# PBag.net
KiCad netlist of a schematic drawn in EAGLE
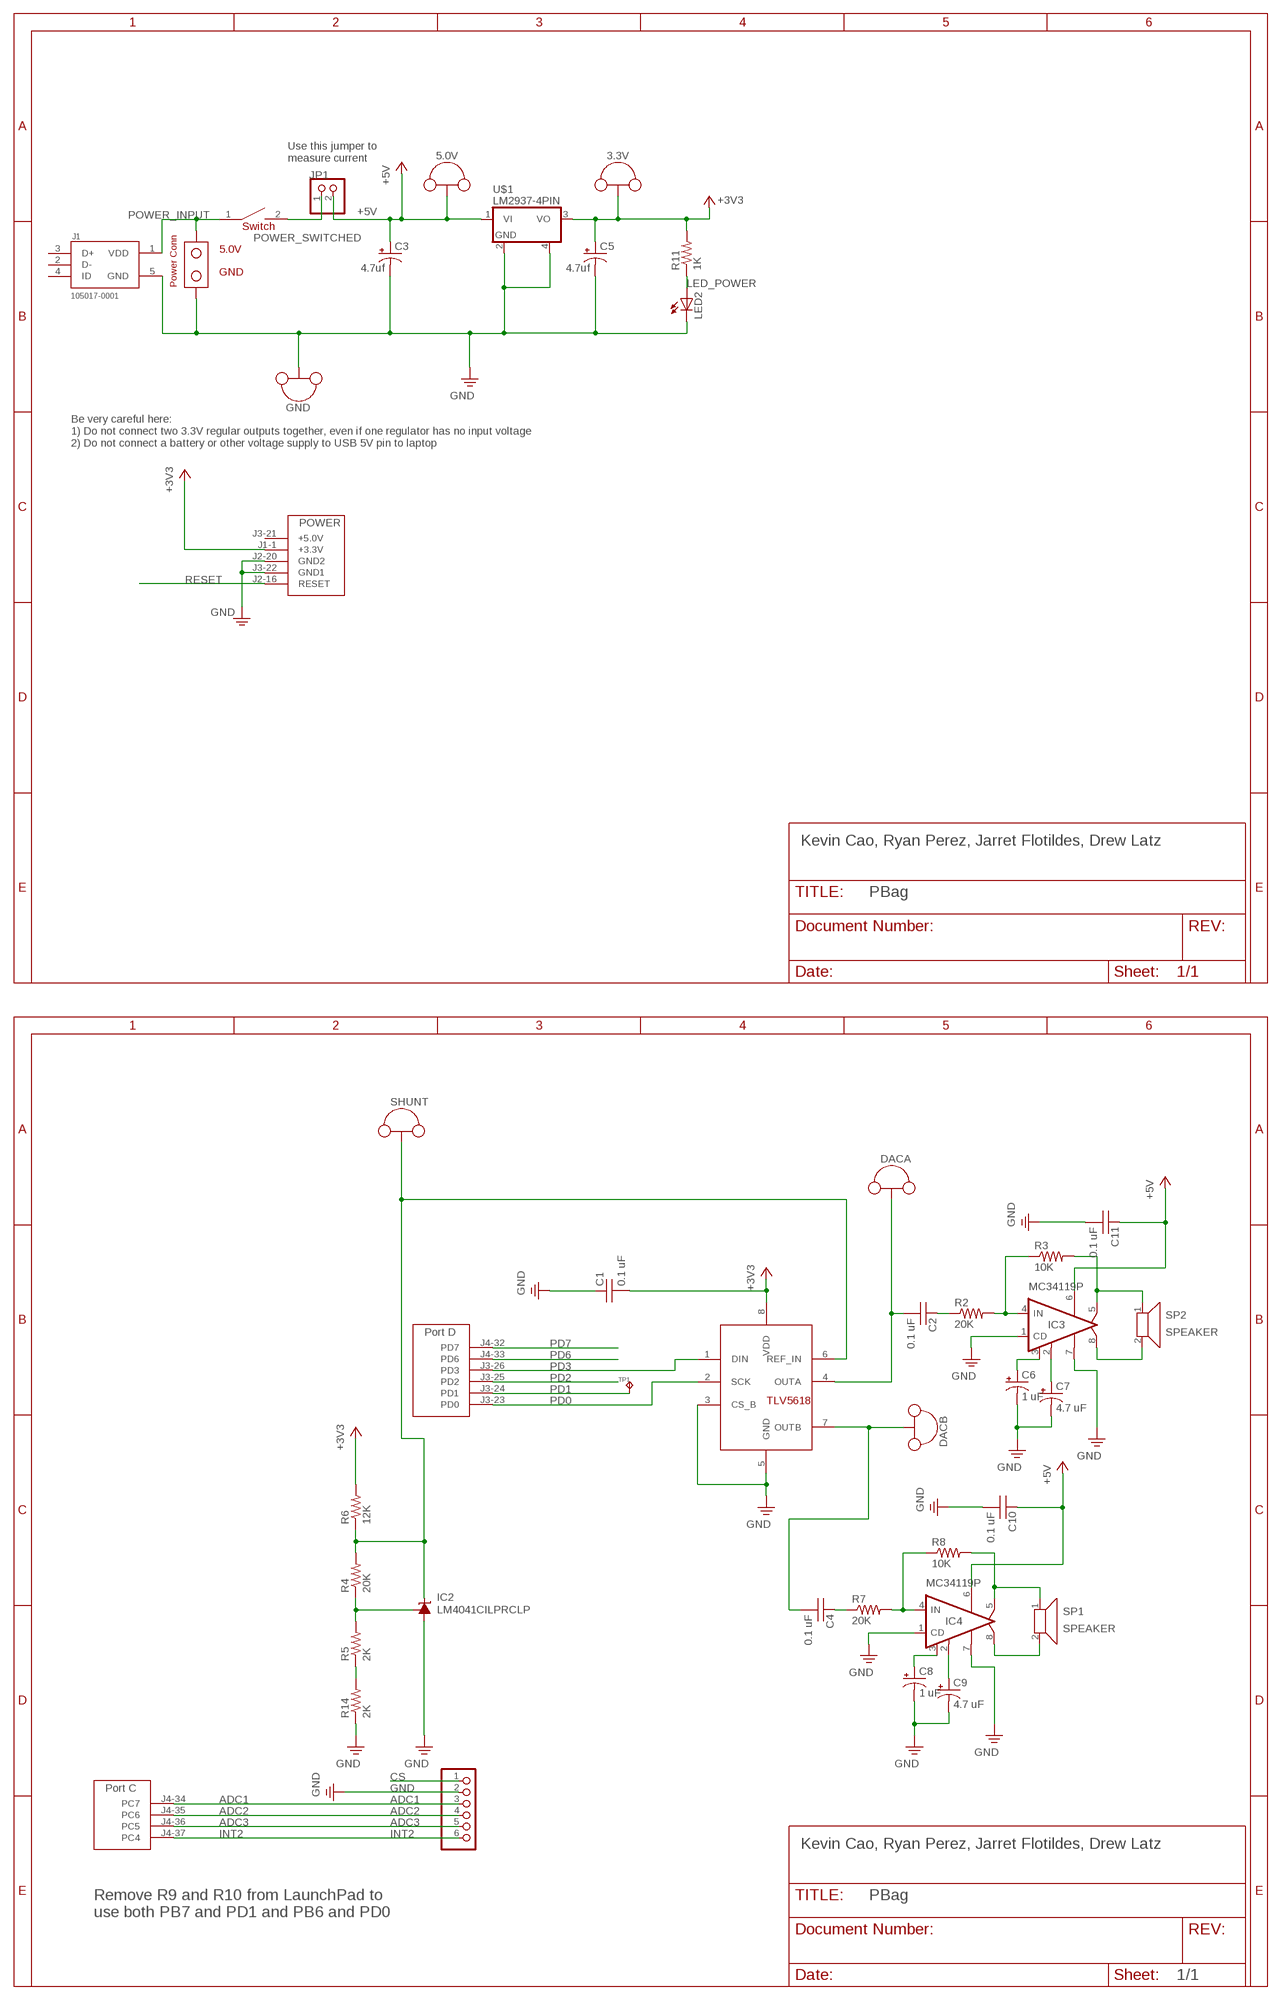
[diagram p0: schematic, sheet 1, part 1 of 2]
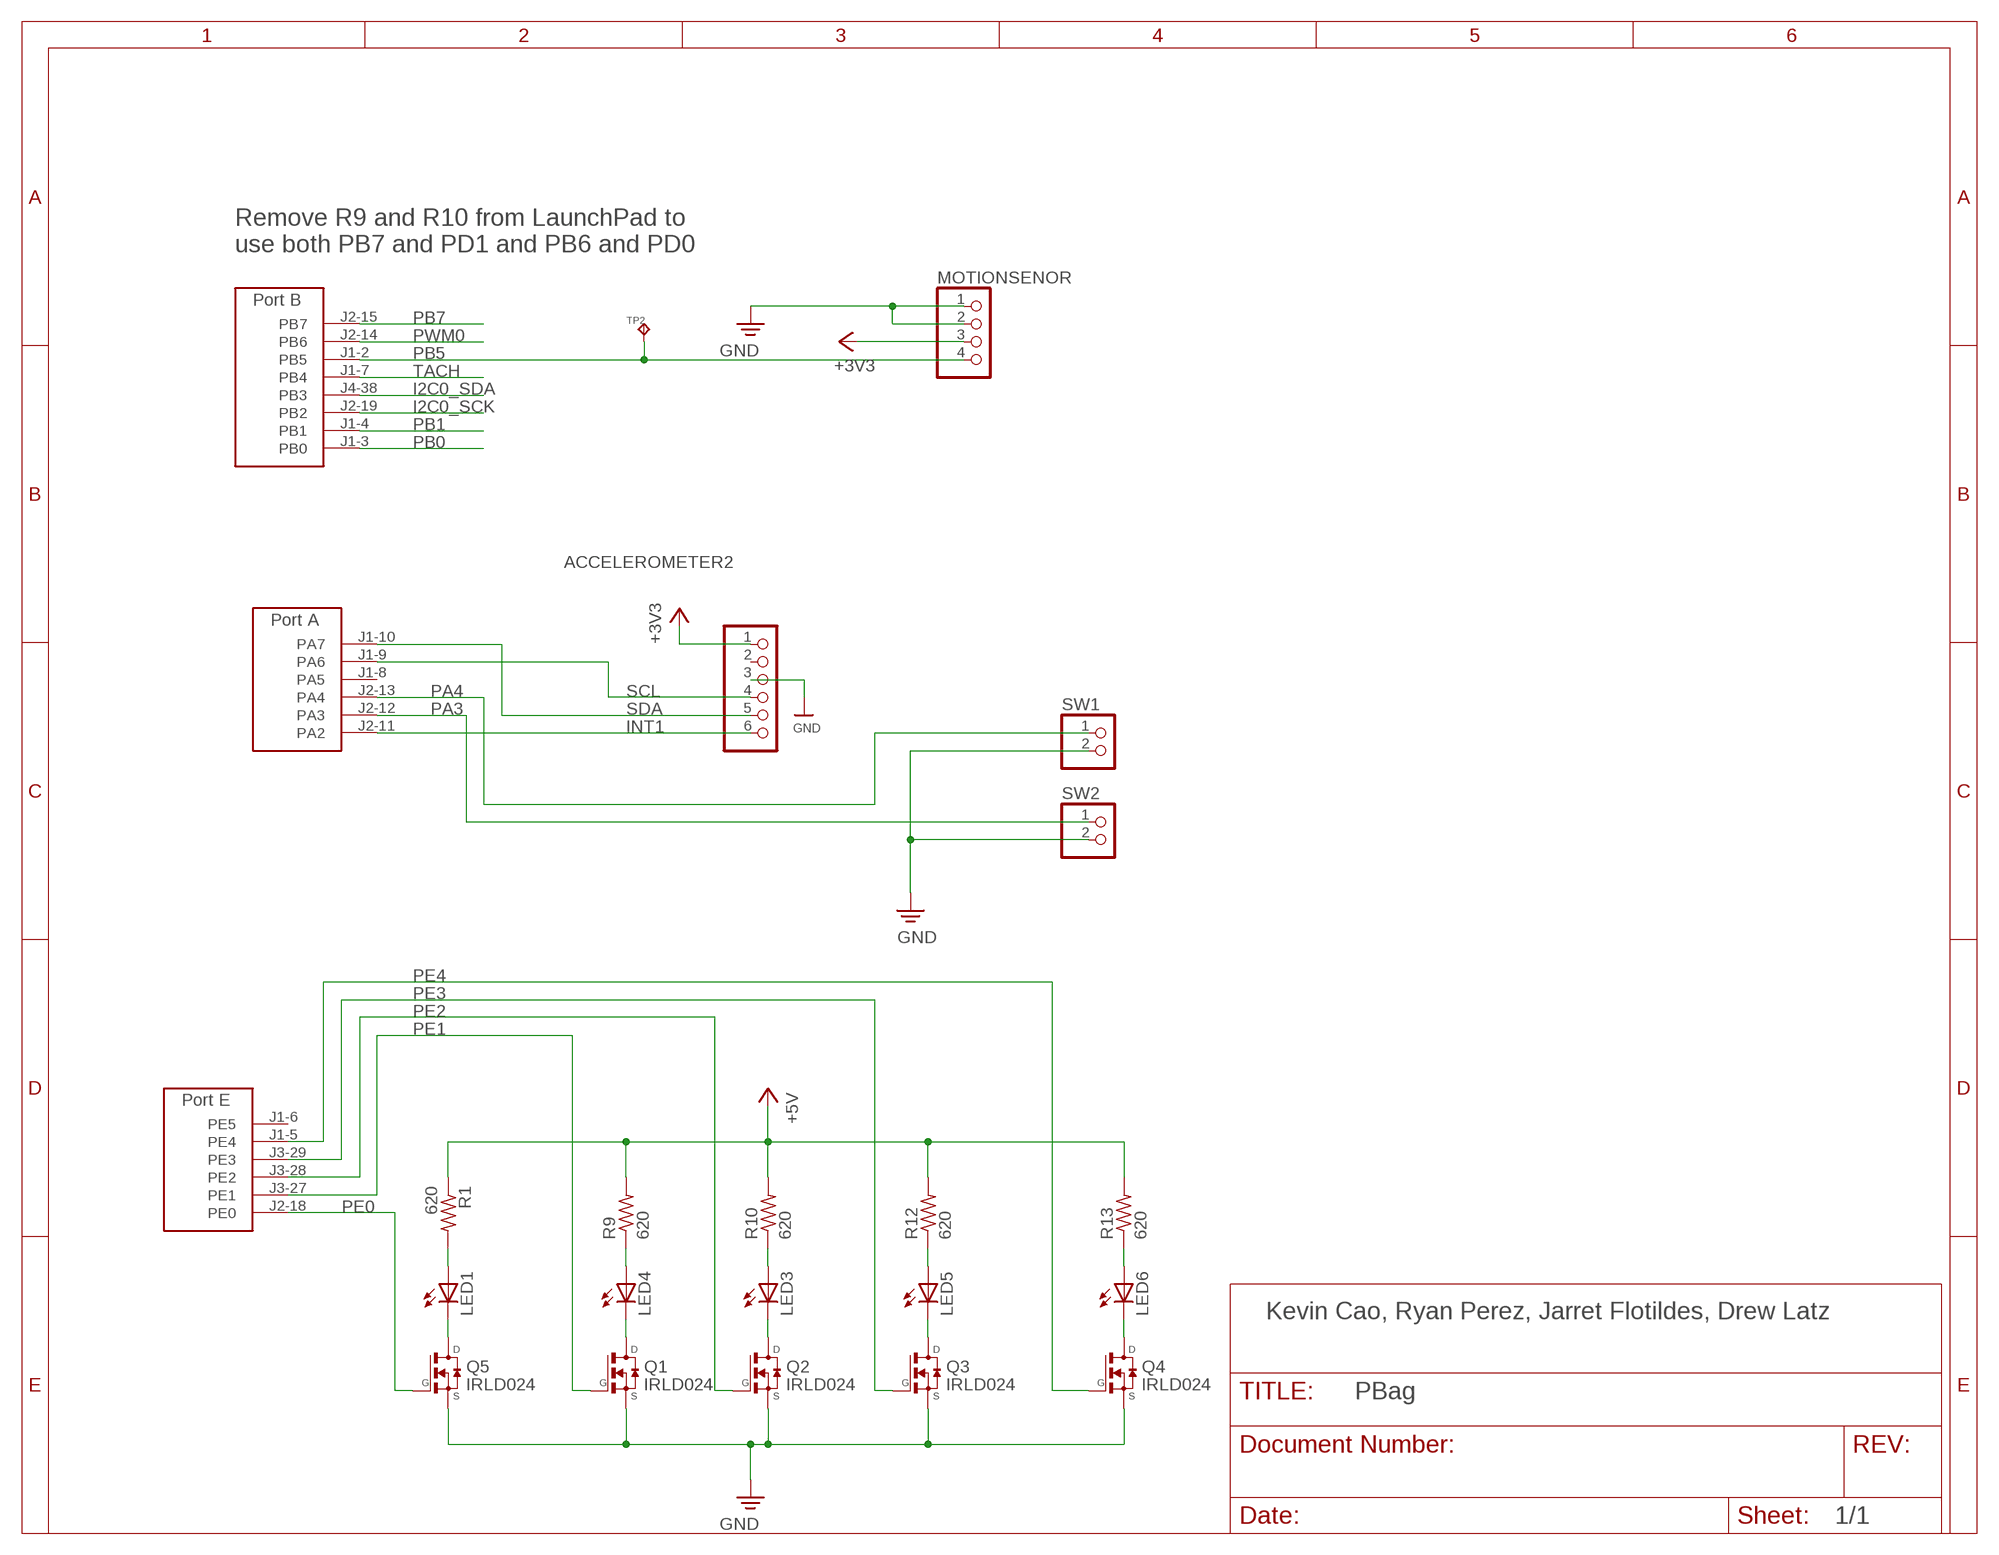
[diagram p1: schematic, sheet 1, part 2 of 2]

(export (version "E")
  (design (tool "Eeschema 10.0.6"))
  (components
    (comp (ref "3.3V")
      (value "TP_LOOP")
      (footprint "eagle-import:TP_LOOP")
      (libsource (lib "eagle-import") (part "TP_LOOP"))
    )
    (comp (ref "5.0V")
      (value "TP_LOOP")
      (footprint "eagle-import:TP_LOOP")
      (libsource (lib "eagle-import") (part "TP_LOOP"))
    )
    (comp (ref "ACCELEROMETER1")
      (value "HEADER-1X670MIL")
      (footprint "eagle-import:1X06_ROUND_70")
      (libsource (lib "eagle-import") (part "HEADER-1X670MIL"))
    )
    (comp (ref "ACCELEROMETER2")
      (value "HEADER-1X670MIL")
      (footprint "eagle-import:1X06_ROUND_70")
      (libsource (lib "eagle-import") (part "HEADER-1X670MIL"))
    )
    (comp (ref "C1")
      (value "0.1 uF")
      (footprint "eagle-import:CAP100MIL")
      (libsource (lib "eagle-import") (part "EE445L (1)_CAPACITOR025-024X044"))
    )
    (comp (ref "C2")
      (value "0.1 uF")
      (footprint "eagle-import:CAP100MIL")
      (libsource (lib "eagle-import") (part "EE445L (1)_CAPACITOR025-024X044"))
    )
    (comp (ref "C3")
      (value "4.7uf")
      (footprint "eagle-import:CAP200MILPOLARIZED")
      (libsource (lib "eagle-import") (part "CAPACITOR_POLARIZEDE5-6"))
    )
    (comp (ref "C4")
      (value "0.1 uF")
      (footprint "eagle-import:CAP100MIL")
      (libsource (lib "eagle-import") (part "EE445L (1)_CAPACITOR025-024X044"))
    )
    (comp (ref "C5")
      (value "4.7uf")
      (footprint "eagle-import:CAP200MILPOLARIZED")
      (libsource (lib "eagle-import") (part "CAPACITOR_POLARIZEDE5-6"))
    )
    (comp (ref "C6")
      (value "1 uF")
      (footprint "eagle-import:CAP200MILPOLARIZED")
      (libsource (lib "eagle-import") (part "EE445L (1)_CAPACITOR_POLARIZEDE5-6"))
    )
    (comp (ref "C7")
      (value "4.7 uF")
      (footprint "eagle-import:CAP200MILPOLARIZED")
      (libsource (lib "eagle-import") (part "EE445L (1)_CAPACITOR_POLARIZEDE5-6"))
    )
    (comp (ref "C8")
      (value "1 uF")
      (footprint "eagle-import:CAP200MILPOLARIZED")
      (libsource (lib "eagle-import") (part "EE445L (1)_CAPACITOR_POLARIZEDE5-6"))
    )
    (comp (ref "C9")
      (value "4.7 uF")
      (footprint "eagle-import:CAP200MILPOLARIZED")
      (libsource (lib "eagle-import") (part "EE445L (1)_CAPACITOR_POLARIZEDE5-6"))
    )
    (comp (ref "C10")
      (value "0.1 uF")
      (footprint "eagle-import:CAP100MIL")
      (libsource (lib "eagle-import") (part "CAPACITOR025-024X044"))
    )
    (comp (ref "C11")
      (value "0.1 uF")
      (footprint "eagle-import:CAP100MIL")
      (libsource (lib "eagle-import") (part "CAPACITOR025-024X044"))
    )
    (comp (ref "DAC")
      (value "TLV5618")
      (footprint "eagle-import:DIL08")
      (libsource (lib "eagle-import") (part "TLV5618"))
    )
    (comp (ref "DACA")
      (value "TP_LOOP")
      (footprint "eagle-import:TP_LOOP")
      (libsource (lib "eagle-import") (part "TP_LOOP"))
    )
    (comp (ref "DACB")
      (value "TP_LOOP")
      (footprint "eagle-import:TP_LOOP")
      (libsource (lib "eagle-import") (part "TP_LOOP"))
    )
    (comp (ref "GND")
      (value "TP_LOOP")
      (footprint "eagle-import:TP_LOOP")
      (libsource (lib "eagle-import") (part "TP_LOOP"))
    )
    (comp (ref "IC2")
      (value "LM4041CILPRCLP")
      (footprint "eagle-import:LP_O-PBCY-W3")
      (fields (field (name "MPN") "LM4041CILP"))
      (libsource (lib "eagle-import") (part "LM4041CILPRLPC"))
    )
    (comp (ref "IC3")
      (value "MC34119P")
      (footprint "eagle-import:DIL08")
      (libsource (lib "eagle-import") (part "MC34119P"))
    )
    (comp (ref "IC4")
      (value "MC34119P")
      (footprint "eagle-import:DIL08")
      (libsource (lib "eagle-import") (part "MC34119P"))
    )
    (comp (ref "J1")
      (value "105017-0001")
      (footprint "eagle-import:MOLEX_105017-0001")
      (fields (field (name "MF") "Molex"))
      (libsource (lib "eagle-import") (part "105017-0001"))
    )
    (comp (ref "JP1")
      (value "PINHD-1X2")
      (footprint "eagle-import:1X02")
      (libsource (lib "eagle-import") (part "PINHD-1X2"))
    )
    (comp (ref "LED1")
      (value "LED5MM")
      (footprint "eagle-import:LED5MM")
      (libsource (lib "eagle-import") (part "EE445L (3)_LED5MM"))
    )
    (comp (ref "LED2")
      (value "LED3MM")
      (footprint "eagle-import:LED3MM")
      (libsource (lib "eagle-import") (part "LED3MM"))
    )
    (comp (ref "LED3")
      (value "LED5MM")
      (footprint "eagle-import:LED5MM")
      (libsource (lib "eagle-import") (part "EE445L (3)_LED5MM"))
    )
    (comp (ref "LED4")
      (value "LED5MM")
      (footprint "eagle-import:LED5MM")
      (libsource (lib "eagle-import") (part "EE445L (3)_LED5MM"))
    )
    (comp (ref "LED5")
      (value "LED5MM")
      (footprint "eagle-import:LED5MM")
      (libsource (lib "eagle-import") (part "EE445L (3)_LED5MM"))
    )
    (comp (ref "LED6")
      (value "LED5MM")
      (footprint "eagle-import:LED5MM")
      (libsource (lib "eagle-import") (part "EE445L (3)_LED5MM"))
    )
    (comp (ref "MOTIONSENOR")
      (value "PINHD-1X4/90")
      (footprint "eagle-import:1X04_90")
      (libsource (lib "eagle-import") (part "PINHD-1X4/90"))
    )
    (comp (ref "Q1")
      (value "IRLD024")
      (footprint "eagle-import:IRLD024")
      (libsource (lib "eagle-import") (part "IRLD024"))
    )
    (comp (ref "Q2")
      (value "IRLD024")
      (footprint "eagle-import:IRLD024")
      (libsource (lib "eagle-import") (part "IRLD024"))
    )
    (comp (ref "Q3")
      (value "IRLD024")
      (footprint "eagle-import:IRLD024")
      (libsource (lib "eagle-import") (part "IRLD024"))
    )
    (comp (ref "Q4")
      (value "IRLD024")
      (footprint "eagle-import:IRLD024")
      (libsource (lib "eagle-import") (part "IRLD024"))
    )
    (comp (ref "Q5")
      (value "IRLD024")
      (footprint "eagle-import:IRLD024")
      (libsource (lib "eagle-import") (part "IRLD024"))
    )
    (comp (ref "R1")
      (value "620")
      (footprint "eagle-import:RES200MIL")
      (libsource (lib "eagle-import") (part "EE445L (3)_RESISTOR0204/5"))
    )
    (comp (ref "R2")
      (value "20K")
      (footprint "eagle-import:RES200MIL")
      (libsource (lib "eagle-import") (part "EE445L (1)_RESISTOR0204/5"))
    )
    (comp (ref "R3")
      (value "10K")
      (footprint "eagle-import:RES200MIL")
      (libsource (lib "eagle-import") (part "EE445L (1)_RESISTOR0204/5"))
    )
    (comp (ref "R4")
      (value "20K")
      (footprint "eagle-import:RES200MIL")
      (libsource (lib "eagle-import") (part "RESISTOR0204/5"))
    )
    (comp (ref "R5")
      (value "2K")
      (footprint "eagle-import:RES200MIL")
      (libsource (lib "eagle-import") (part "RESISTOR0204/5"))
    )
    (comp (ref "R6")
      (value "12K")
      (footprint "eagle-import:RES200MIL")
      (libsource (lib "eagle-import") (part "RESISTOR0204/5"))
    )
    (comp (ref "R7")
      (value "20K")
      (footprint "eagle-import:RES200MIL")
      (libsource (lib "eagle-import") (part "EE445L (1)_RESISTOR0204/5"))
    )
    (comp (ref "R8")
      (value "10K")
      (footprint "eagle-import:RES200MIL")
      (libsource (lib "eagle-import") (part "EE445L (1)_RESISTOR0204/5"))
    )
    (comp (ref "R9")
      (value "620")
      (footprint "eagle-import:RES200MIL")
      (libsource (lib "eagle-import") (part "EE445L (3)_RESISTOR0204/5"))
    )
    (comp (ref "R10")
      (value "620")
      (footprint "eagle-import:RES200MIL")
      (libsource (lib "eagle-import") (part "EE445L (3)_RESISTOR0204/5"))
    )
    (comp (ref "R11")
      (value "1K")
      (footprint "eagle-import:RES200MIL")
      (libsource (lib "eagle-import") (part "RESISTOR0204/5"))
    )
    (comp (ref "R12")
      (value "620")
      (footprint "eagle-import:RES200MIL")
      (libsource (lib "eagle-import") (part "EE445L (3)_RESISTOR0204/5"))
    )
    (comp (ref "R13")
      (value "620")
      (footprint "eagle-import:RES200MIL")
      (libsource (lib "eagle-import") (part "EE445L (3)_RESISTOR0204/5"))
    )
    (comp (ref "R14")
      (value "2K")
      (footprint "eagle-import:RES200MIL")
      (libsource (lib "eagle-import") (part "RESISTOR0204/5"))
    )
    (comp (ref "SHUNT")
      (value "TP_LOOP")
      (footprint "eagle-import:TP_LOOP")
      (libsource (lib "eagle-import") (part "TP_LOOP"))
    )
    (comp (ref "SP1")
      (value "SPEAKER")
      (footprint "eagle-import:1X02")
      (libsource (lib "eagle-import") (part "SPEAKER"))
    )
    (comp (ref "SP2")
      (value "SPEAKER")
      (footprint "eagle-import:1X02")
      (libsource (lib "eagle-import") (part "SPEAKER"))
    )
    (comp (ref "SW1")
      (value "PINHD-1X2")
      (footprint "eagle-import:1X02")
      (libsource (lib "eagle-import") (part "PINHD-1X2"))
    )
    (comp (ref "SW2")
      (value "PINHD-1X2")
      (footprint "eagle-import:1X02")
      (libsource (lib "eagle-import") (part "PINHD-1X2"))
    )
    (comp (ref "TP1")
      (value "TP_KEYSTONE500X")
      (footprint "eagle-import:P1.1MM")
      (libsource (lib "eagle-import") (part "TP_KEYSTONE500X"))
    )
    (comp (ref "TP2")
      (value "TP_KEYSTONE500X")
      (footprint "eagle-import:P1.1MM")
      (libsource (lib "eagle-import") (part "TP_KEYSTONE500X"))
    )
    (comp (ref "U$1")
      (value "LM2937-4PIN")
      (footprint "eagle-import:TO220-4PIN")
      (libsource (lib "eagle-import") (part "LM2937-4PIN"))
    )
    (comp (ref "U$2")
      (value "TM4C_BP")
      (footprint "eagle-import:TM4C_BOOSTER_PACK")
      (libsource (lib "eagle-import") (part "TM4C_BP"))
    )
    (comp (ref "U$5")
      (value "POWER_CONN")
      (footprint "eagle-import:POWER_CONN")
      (libsource (lib "eagle-import") (part "POWER_CONN"))
    )
    (comp (ref "U$6")
      (value "SW_POWER_100MIL")
      (footprint "eagle-import:SW_POWER")
      (libsource (lib "eagle-import") (part "SW_POWER_100MIL"))
    )
  )
  (nets
    (net (code "1") (name "+3V3") (class "Default")
      (node (ref "3.3V") (pin "P$1") (pinfunction "TP_P$1") (pintype "bidirectional"))
      (node (ref "3.3V") (pin "P$2") (pinfunction "TP_P$2") (pintype "bidirectional"))
      (node (ref "ACCELEROMETER2") (pin "1") (pinfunction "1_1") (pintype "passive"))
      (node (ref "C1") (pin "2") (pinfunction "2_2") (pintype "passive"))
      (node (ref "C5") (pin "+") (pinfunction "+_+") (pintype "passive"))
      (node (ref "DAC") (pin "8") (pinfunction "VDD_8") (pintype "bidirectional"))
      (node (ref "MOTIONSENOR") (pin "3") (pinfunction "3_3") (pintype "passive"))
      (node (ref "R11") (pin "2") (pinfunction "2_2") (pintype "passive"))
      (node (ref "R6") (pin "2") (pinfunction "2_2") (pintype "passive"))
      (node (ref "U$1") (pin "3") (pinfunction "VO_3") (pintype "passive"))
      (node (ref "U$2") (pin "J1-1") (pinfunction "+3.3V_J1-1") (pintype "bidirectional"))
    )
    (net (code "2") (name "+5V") (class "Default")
      (node (ref "5.0V") (pin "P$1") (pinfunction "TP_P$1") (pintype "bidirectional"))
      (node (ref "5.0V") (pin "P$2") (pinfunction "TP_P$2") (pintype "bidirectional"))
      (node (ref "C10") (pin "1") (pinfunction "1_1") (pintype "passive"))
      (node (ref "C11") (pin "1") (pinfunction "1_1") (pintype "passive"))
      (node (ref "C3") (pin "+") (pinfunction "+_+") (pintype "passive"))
      (node (ref "IC3") (pin "6") (pinfunction "VCC_6") (pintype "power_in"))
      (node (ref "IC4") (pin "6") (pinfunction "VCC_6") (pintype "power_in"))
      (node (ref "JP1") (pin "2") (pinfunction "2_2") (pintype "passive"))
      (node (ref "R1") (pin "1") (pinfunction "1_1") (pintype "passive"))
      (node (ref "R10") (pin "2") (pinfunction "2_2") (pintype "passive"))
      (node (ref "R12") (pin "2") (pinfunction "2_2") (pintype "passive"))
      (node (ref "R13") (pin "2") (pinfunction "2_2") (pintype "passive"))
      (node (ref "R9") (pin "2") (pinfunction "2_2") (pintype "passive"))
      (node (ref "U$1") (pin "1") (pinfunction "VI_1") (pintype "input"))
    )
    (net (code "3") (name "/ADC1") (class "Default")
      (node (ref "ACCELEROMETER1") (pin "3") (pinfunction "3_3") (pintype "passive"))
      (node (ref "U$2") (pin "J4-34") (pinfunction "PC7_J4-34") (pintype "bidirectional"))
    )
    (net (code "4") (name "/ADC2") (class "Default")
      (node (ref "ACCELEROMETER1") (pin "4") (pinfunction "4_4") (pintype "passive"))
      (node (ref "U$2") (pin "J4-35") (pinfunction "PC6_J4-35") (pintype "bidirectional"))
    )
    (net (code "5") (name "/ADC3") (class "Default")
      (node (ref "ACCELEROMETER1") (pin "5") (pinfunction "5_5") (pintype "passive"))
      (node (ref "U$2") (pin "J4-36") (pinfunction "PC5_J4-36") (pintype "bidirectional"))
    )
    (net (code "6") (name "/CS") (class "Default")
      (node (ref "ACCELEROMETER1") (pin "1") (pinfunction "1_1") (pintype "passive"))
    )
    (net (code "7") (name "/I2C0_SCK") (class "Default")
      (node (ref "U$2") (pin "J2-19") (pinfunction "PB2_J2-19") (pintype "bidirectional"))
    )
    (net (code "8") (name "/I2C0_SDA") (class "Default")
      (node (ref "U$2") (pin "J4-38") (pinfunction "PB3_J4-38") (pintype "bidirectional"))
    )
    (net (code "9") (name "/INT1") (class "Default")
      (node (ref "ACCELEROMETER2") (pin "6") (pinfunction "6_6") (pintype "passive"))
      (node (ref "U$2") (pin "J2-11") (pinfunction "PA2_J2-11") (pintype "bidirectional"))
    )
    (net (code "10") (name "/INT2") (class "Default")
      (node (ref "ACCELEROMETER1") (pin "6") (pinfunction "6_6") (pintype "passive"))
      (node (ref "U$2") (pin "J4-37") (pinfunction "PC4_J4-37") (pintype "bidirectional"))
    )
    (net (code "11") (name "/LED_POWER") (class "Default")
      (node (ref "LED2") (pin "A") (pinfunction "A_A") (pintype "passive"))
      (node (ref "R11") (pin "1") (pinfunction "1_1") (pintype "passive"))
    )
    (net (code "12") (name "/PA3") (class "Default")
      (node (ref "SW2") (pin "1") (pinfunction "1_1") (pintype "passive"))
      (node (ref "U$2") (pin "J2-12") (pinfunction "PA3_J2-12") (pintype "bidirectional"))
    )
    (net (code "13") (name "/PA4") (class "Default")
      (node (ref "SW1") (pin "1") (pinfunction "1_1") (pintype "passive"))
      (node (ref "U$2") (pin "J2-13") (pinfunction "PA4_J2-13") (pintype "bidirectional"))
    )
    (net (code "14") (name "/PB0") (class "Default")
      (node (ref "U$2") (pin "J1-3") (pinfunction "PB0_J1-3") (pintype "bidirectional"))
    )
    (net (code "15") (name "/PB1") (class "Default")
      (node (ref "U$2") (pin "J1-4") (pinfunction "PB1_J1-4") (pintype "bidirectional"))
    )
    (net (code "16") (name "/PB5") (class "Default")
      (node (ref "MOTIONSENOR") (pin "4") (pinfunction "4_4") (pintype "passive"))
      (node (ref "TP2") (pin "TP") (pinfunction "TP_TP") (pintype "input"))
      (node (ref "U$2") (pin "J1-2") (pinfunction "PB5_J1-2") (pintype "bidirectional"))
    )
    (net (code "17") (name "/PB7") (class "Default")
      (node (ref "U$2") (pin "J2-15") (pinfunction "PB7_J2-15") (pintype "bidirectional"))
    )
    (net (code "18") (name "/PD0") (class "Default")
      (node (ref "DAC") (pin "2") (pinfunction "SCK_2") (pintype "bidirectional"))
      (node (ref "U$2") (pin "J3-23") (pinfunction "PD0_J3-23") (pintype "bidirectional"))
    )
    (net (code "19") (name "/PD1") (class "Default")
      (node (ref "TP1") (pin "TP") (pinfunction "TP_TP") (pintype "input"))
      (node (ref "U$2") (pin "J3-24") (pinfunction "PD1_J3-24") (pintype "bidirectional"))
    )
    (net (code "20") (name "/PD2") (class "Default")
      (node (ref "U$2") (pin "J3-25") (pinfunction "PD2_J3-25") (pintype "bidirectional"))
    )
    (net (code "21") (name "/PD3") (class "Default")
      (node (ref "DAC") (pin "1") (pinfunction "DIN_1") (pintype "bidirectional"))
      (node (ref "U$2") (pin "J3-26") (pinfunction "PD3_J3-26") (pintype "bidirectional"))
    )
    (net (code "22") (name "/PD6") (class "Default")
      (node (ref "U$2") (pin "J4-33") (pinfunction "PD6_J4-33") (pintype "bidirectional"))
    )
    (net (code "23") (name "/PD7") (class "Default")
      (node (ref "U$2") (pin "J4-32") (pinfunction "PD7_J4-32") (pintype "bidirectional"))
    )
    (net (code "24") (name "/PE0") (class "Default")
      (node (ref "Q5") (pin "P$3") (pinfunction "G_P$3") (pintype "passive"))
      (node (ref "U$2") (pin "J2-18") (pinfunction "PE0_J2-18") (pintype "bidirectional"))
    )
    (net (code "25") (name "/PE1") (class "Default")
      (node (ref "Q1") (pin "P$3") (pinfunction "G_P$3") (pintype "passive"))
      (node (ref "U$2") (pin "J3-27") (pinfunction "PE1_J3-27") (pintype "bidirectional"))
    )
    (net (code "26") (name "/PE2") (class "Default")
      (node (ref "Q2") (pin "P$3") (pinfunction "G_P$3") (pintype "passive"))
      (node (ref "U$2") (pin "J3-28") (pinfunction "PE2_J3-28") (pintype "bidirectional"))
    )
    (net (code "27") (name "/PE3") (class "Default")
      (node (ref "Q3") (pin "P$3") (pinfunction "G_P$3") (pintype "passive"))
      (node (ref "U$2") (pin "J3-29") (pinfunction "PE3_J3-29") (pintype "bidirectional"))
    )
    (net (code "28") (name "/PE4") (class "Default")
      (node (ref "Q4") (pin "P$3") (pinfunction "G_P$3") (pintype "passive"))
      (node (ref "U$2") (pin "J1-5") (pinfunction "PE4_J1-5") (pintype "bidirectional"))
    )
    (net (code "29") (name "/POWER_INPUT") (class "Default")
      (node (ref "J1") (pin "1") (pinfunction "VDD_1") (pintype "power_in"))
      (node (ref "U$5") (pin "VDD") (pinfunction "VDD_VDD") (pintype "bidirectional"))
      (node (ref "U$6") (pin "1") (pinfunction "P$1_1") (pintype "bidirectional"))
    )
    (net (code "30") (name "/POWER_SWITCHED") (class "Default")
      (node (ref "JP1") (pin "1") (pinfunction "1_1") (pintype "passive"))
      (node (ref "U$6") (pin "2") (pinfunction "P$2_2") (pintype "bidirectional"))
    )
    (net (code "31") (name "/PWM0") (class "Default")
      (node (ref "U$2") (pin "J2-14") (pinfunction "PB6_J2-14") (pintype "bidirectional"))
    )
    (net (code "32") (name "/RESET") (class "Default")
      (node (ref "U$2") (pin "J2-16") (pinfunction "RESET_J2-16") (pintype "bidirectional"))
    )
    (net (code "33") (name "/SCL") (class "Default")
      (node (ref "ACCELEROMETER2") (pin "4") (pinfunction "4_4") (pintype "passive"))
      (node (ref "U$2") (pin "J1-9") (pinfunction "PA6_J1-9") (pintype "bidirectional"))
    )
    (net (code "34") (name "/SDA") (class "Default")
      (node (ref "ACCELEROMETER2") (pin "5") (pinfunction "5_5") (pintype "passive"))
      (node (ref "U$2") (pin "J1-10") (pinfunction "PA7_J1-10") (pintype "bidirectional"))
    )
    (net (code "35") (name "/TACH") (class "Default")
      (node (ref "U$2") (pin "J1-7") (pinfunction "PB4_J1-7") (pintype "bidirectional"))
    )
    (net (code "36") (name "GND") (class "Default")
      (node (ref "ACCELEROMETER1") (pin "2") (pinfunction "2_2") (pintype "passive"))
      (node (ref "ACCELEROMETER2") (pin "3") (pinfunction "3_3") (pintype "passive"))
      (node (ref "C1") (pin "1") (pinfunction "1_1") (pintype "passive"))
      (node (ref "C10") (pin "2") (pinfunction "2_2") (pintype "passive"))
      (node (ref "C11") (pin "2") (pinfunction "2_2") (pintype "passive"))
      (node (ref "C3") (pin "-") (pinfunction "-_-") (pintype "passive"))
      (node (ref "C5") (pin "-") (pinfunction "-_-") (pintype "passive"))
      (node (ref "C6") (pin "-") (pinfunction "-_-") (pintype "passive"))
      (node (ref "C7") (pin "-") (pinfunction "-_-") (pintype "passive"))
      (node (ref "C8") (pin "-") (pinfunction "-_-") (pintype "passive"))
      (node (ref "C9") (pin "-") (pinfunction "-_-") (pintype "passive"))
      (node (ref "DAC") (pin "3") (pinfunction "CS_B_3") (pintype "bidirectional"))
      (node (ref "DAC") (pin "5") (pinfunction "GND_5") (pintype "bidirectional"))
      (node (ref "GND") (pin "P$1") (pinfunction "TP_P$1") (pintype "bidirectional"))
      (node (ref "GND") (pin "P$2") (pinfunction "TP_P$2") (pintype "bidirectional"))
      (node (ref "IC2") (pin "3") (pinfunction "A_3") (pintype "passive"))
      (node (ref "IC3") (pin "1") (pinfunction "CD_1") (pintype "passive"))
      (node (ref "IC3") (pin "7") (pinfunction "GND_7") (pintype "power_in"))
      (node (ref "IC4") (pin "1") (pinfunction "CD_1") (pintype "passive"))
      (node (ref "IC4") (pin "7") (pinfunction "GND_7") (pintype "power_in"))
      (node (ref "J1") (pin "5") (pinfunction "GND_5") (pintype "power_in"))
      (node (ref "LED2") (pin "K") (pinfunction "C_K") (pintype "passive"))
      (node (ref "MOTIONSENOR") (pin "1") (pinfunction "1_1") (pintype "passive"))
      (node (ref "MOTIONSENOR") (pin "2") (pinfunction "2_2") (pintype "passive"))
      (node (ref "Q1") (pin "P$4") (pinfunction "S_P$4") (pintype "passive"))
      (node (ref "Q2") (pin "P$4") (pinfunction "S_P$4") (pintype "passive"))
      (node (ref "Q3") (pin "P$4") (pinfunction "S_P$4") (pintype "passive"))
      (node (ref "Q4") (pin "P$4") (pinfunction "S_P$4") (pintype "passive"))
      (node (ref "Q5") (pin "P$4") (pinfunction "S_P$4") (pintype "passive"))
      (node (ref "R14") (pin "1") (pinfunction "1_1") (pintype "passive"))
      (node (ref "SW1") (pin "2") (pinfunction "2_2") (pintype "passive"))
      (node (ref "SW2") (pin "2") (pinfunction "2_2") (pintype "passive"))
      (node (ref "U$1") (pin "2") (pinfunction "GND_2") (pintype "passive"))
      (node (ref "U$1") (pin "4") (pinfunction "PAD_4") (pintype "passive"))
      (node (ref "U$2") (pin "J2-20") (pinfunction "GND2_J2-20") (pintype "bidirectional"))
      (node (ref "U$2") (pin "J3-22") (pinfunction "GND1_J3-22") (pintype "bidirectional"))
      (node (ref "U$5") (pin "GND") (pinfunction "GND_GND") (pintype "bidirectional"))
    )
    (net (code "37") (name "Net-(C2-Pad1)") (class "Default")
      (node (ref "C2") (pin "1") (pinfunction "1_1") (pintype "passive"))
      (node (ref "R2") (pin "1") (pinfunction "1_1") (pintype "passive"))
    )
    (net (code "38") (name "Net-(C4-Pad1)") (class "Default")
      (node (ref "C4") (pin "1") (pinfunction "1_1") (pintype "passive"))
      (node (ref "R7") (pin "1") (pinfunction "1_1") (pintype "passive"))
    )
    (net (code "39") (name "Net-(DAC-OUTA)") (class "Default")
      (node (ref "C2") (pin "2") (pinfunction "2_2") (pintype "passive"))
      (node (ref "DAC") (pin "4") (pinfunction "OUTA_4") (pintype "bidirectional"))
      (node (ref "DACA") (pin "P$1") (pinfunction "TP_P$1") (pintype "bidirectional"))
      (node (ref "DACA") (pin "P$2") (pinfunction "TP_P$2") (pintype "bidirectional"))
    )
    (net (code "40") (name "Net-(DAC-OUTB)") (class "Default")
      (node (ref "C4") (pin "2") (pinfunction "2_2") (pintype "passive"))
      (node (ref "DAC") (pin "7") (pinfunction "OUTB_7") (pintype "bidirectional"))
      (node (ref "DACB") (pin "P$1") (pinfunction "TP_P$1") (pintype "bidirectional"))
      (node (ref "DACB") (pin "P$2") (pinfunction "TP_P$2") (pintype "bidirectional"))
    )
    (net (code "41") (name "Net-(DAC-REF_IN)") (class "Default")
      (node (ref "DAC") (pin "6") (pinfunction "REF_IN_6") (pintype "bidirectional"))
      (node (ref "IC2") (pin "2") (pinfunction "C_2") (pintype "passive"))
      (node (ref "R4") (pin "2") (pinfunction "2_2") (pintype "passive"))
      (node (ref "R6") (pin "1") (pinfunction "1_1") (pintype "passive"))
      (node (ref "SHUNT") (pin "P$1") (pinfunction "TP_P$1") (pintype "bidirectional"))
      (node (ref "SHUNT") (pin "P$2") (pinfunction "TP_P$2") (pintype "bidirectional"))
    )
    (net (code "42") (name "Net-(IC2-FB)") (class "Default")
      (node (ref "IC2") (pin "1") (pinfunction "FB_1") (pintype "passive"))
      (node (ref "R4") (pin "1") (pinfunction "1_1") (pintype "passive"))
      (node (ref "R5") (pin "2") (pinfunction "2_2") (pintype "passive"))
    )
    (net (code "43") (name "Net-(IC3-FC1)") (class "Default")
      (node (ref "C6") (pin "+") (pinfunction "+_+") (pintype "passive"))
      (node (ref "IC3") (pin "3") (pinfunction "FC1_3") (pintype "passive"))
    )
    (net (code "44") (name "Net-(IC3-FC2)") (class "Default")
      (node (ref "C7") (pin "+") (pinfunction "+_+") (pintype "passive"))
      (node (ref "IC3") (pin "2") (pinfunction "FC2_2") (pintype "passive"))
    )
    (net (code "45") (name "Net-(IC3-IN)") (class "Default")
      (node (ref "IC3") (pin "4") (pinfunction "IN_4") (pintype "input"))
      (node (ref "R2") (pin "2") (pinfunction "2_2") (pintype "passive"))
      (node (ref "R3") (pin "1") (pinfunction "1_1") (pintype "passive"))
    )
    (net (code "46") (name "Net-(IC3-VO1)") (class "Default")
      (node (ref "IC3") (pin "5") (pinfunction "VO1_5") (pintype "output"))
      (node (ref "R3") (pin "2") (pinfunction "2_2") (pintype "passive"))
      (node (ref "SP2") (pin "1") (pinfunction "1_1") (pintype "passive"))
    )
    (net (code "47") (name "Net-(IC3-VO2)") (class "Default")
      (node (ref "IC3") (pin "8") (pinfunction "VO2_8") (pintype "output"))
      (node (ref "SP2") (pin "2") (pinfunction "2_2") (pintype "passive"))
    )
    (net (code "48") (name "Net-(IC4-FC1)") (class "Default")
      (node (ref "C8") (pin "+") (pinfunction "+_+") (pintype "passive"))
      (node (ref "IC4") (pin "3") (pinfunction "FC1_3") (pintype "passive"))
    )
    (net (code "49") (name "Net-(IC4-FC2)") (class "Default")
      (node (ref "C9") (pin "+") (pinfunction "+_+") (pintype "passive"))
      (node (ref "IC4") (pin "2") (pinfunction "FC2_2") (pintype "passive"))
    )
    (net (code "50") (name "Net-(IC4-IN)") (class "Default")
      (node (ref "IC4") (pin "4") (pinfunction "IN_4") (pintype "input"))
      (node (ref "R7") (pin "2") (pinfunction "2_2") (pintype "passive"))
      (node (ref "R8") (pin "1") (pinfunction "1_1") (pintype "passive"))
    )
    (net (code "51") (name "Net-(IC4-VO1)") (class "Default")
      (node (ref "IC4") (pin "5") (pinfunction "VO1_5") (pintype "output"))
      (node (ref "R8") (pin "2") (pinfunction "2_2") (pintype "passive"))
      (node (ref "SP1") (pin "1") (pinfunction "1_1") (pintype "passive"))
    )
    (net (code "52") (name "Net-(IC4-VO2)") (class "Default")
      (node (ref "IC4") (pin "8") (pinfunction "VO2_8") (pintype "output"))
      (node (ref "SP1") (pin "2") (pinfunction "2_2") (pintype "passive"))
    )
    (net (code "53") (name "Net-(LED1-C)") (class "Default")
      (node (ref "LED1") (pin "K") (pinfunction "C_K") (pintype "passive"))
      (node (ref "Q5") (pin "P$1") (pinfunction "D_P$1") (pintype "passive"))
    )
    (net (code "54") (name "Net-(LED1-PadA)") (class "Default")
      (node (ref "LED1") (pin "A") (pinfunction "A_A") (pintype "passive"))
      (node (ref "R1") (pin "2") (pinfunction "2_2") (pintype "passive"))
    )
    (net (code "55") (name "Net-(LED3-C)") (class "Default")
      (node (ref "LED3") (pin "K") (pinfunction "C_K") (pintype "passive"))
      (node (ref "Q2") (pin "P$1") (pinfunction "D_P$1") (pintype "passive"))
    )
    (net (code "56") (name "Net-(LED3-PadA)") (class "Default")
      (node (ref "LED3") (pin "A") (pinfunction "A_A") (pintype "passive"))
      (node (ref "R10") (pin "1") (pinfunction "1_1") (pintype "passive"))
    )
    (net (code "57") (name "Net-(LED4-C)") (class "Default")
      (node (ref "LED4") (pin "K") (pinfunction "C_K") (pintype "passive"))
      (node (ref "Q1") (pin "P$1") (pinfunction "D_P$1") (pintype "passive"))
    )
    (net (code "58") (name "Net-(LED4-PadA)") (class "Default")
      (node (ref "LED4") (pin "A") (pinfunction "A_A") (pintype "passive"))
      (node (ref "R9") (pin "1") (pinfunction "1_1") (pintype "passive"))
    )
    (net (code "59") (name "Net-(LED5-C)") (class "Default")
      (node (ref "LED5") (pin "K") (pinfunction "C_K") (pintype "passive"))
      (node (ref "Q3") (pin "P$1") (pinfunction "D_P$1") (pintype "passive"))
    )
    (net (code "60") (name "Net-(LED5-PadA)") (class "Default")
      (node (ref "LED5") (pin "A") (pinfunction "A_A") (pintype "passive"))
      (node (ref "R12") (pin "1") (pinfunction "1_1") (pintype "passive"))
    )
    (net (code "61") (name "Net-(LED6-C)") (class "Default")
      (node (ref "LED6") (pin "K") (pinfunction "C_K") (pintype "passive"))
      (node (ref "Q4") (pin "P$1") (pinfunction "D_P$1") (pintype "passive"))
    )
    (net (code "62") (name "Net-(LED6-PadA)") (class "Default")
      (node (ref "LED6") (pin "A") (pinfunction "A_A") (pintype "passive"))
      (node (ref "R13") (pin "1") (pinfunction "1_1") (pintype "passive"))
    )
    (net (code "63") (name "Net-(R14-Pad2)") (class "Default")
      (node (ref "R14") (pin "2") (pinfunction "2_2") (pintype "passive"))
      (node (ref "R5") (pin "1") (pinfunction "1_1") (pintype "passive"))
    )
    (net (code "64") (name "unconnected-(ACCELEROMETER2-Pad2)") (class "Default")
      (node (ref "ACCELEROMETER2") (pin "2") (pinfunction "2_2") (pintype "passive"))
    )
    (net (code "65") (name "unconnected-(J1-D+-Pad3)") (class "Default")
      (node (ref "J1") (pin "3") (pinfunction "D+_3") (pintype "bidirectional"))
    )
    (net (code "66") (name "unconnected-(J1-D--Pad2)") (class "Default")
      (node (ref "J1") (pin "2") (pinfunction "D-_2") (pintype "bidirectional"))
    )
    (net (code "67") (name "unconnected-(J1-ID-Pad4)") (class "Default")
      (node (ref "J1") (pin "4") (pinfunction "ID_4") (pintype "passive"))
    )
    (net (code "68") (name "unconnected-(U$2A-PA5-PadJ1-8)") (class "Default")
      (node (ref "U$2") (pin "J1-8") (pinfunction "PA5_J1-8") (pintype "bidirectional"))
    )
    (net (code "69") (name "unconnected-(U$2E-PE5-PadJ1-6)") (class "Default")
      (node (ref "U$2") (pin "J1-6") (pinfunction "PE5_J1-6") (pintype "bidirectional"))
    )
    (net (code "70") (name "unconnected-(U$2G-+5.0V-PadJ3-21)") (class "Default")
      (node (ref "U$2") (pin "J3-21") (pinfunction "+5.0V_J3-21") (pintype "bidirectional"))
    )
  )
)
